# qo-100-digital-rf-power-meter.net
KiCad netlist of a schematic drawn in EAGLE
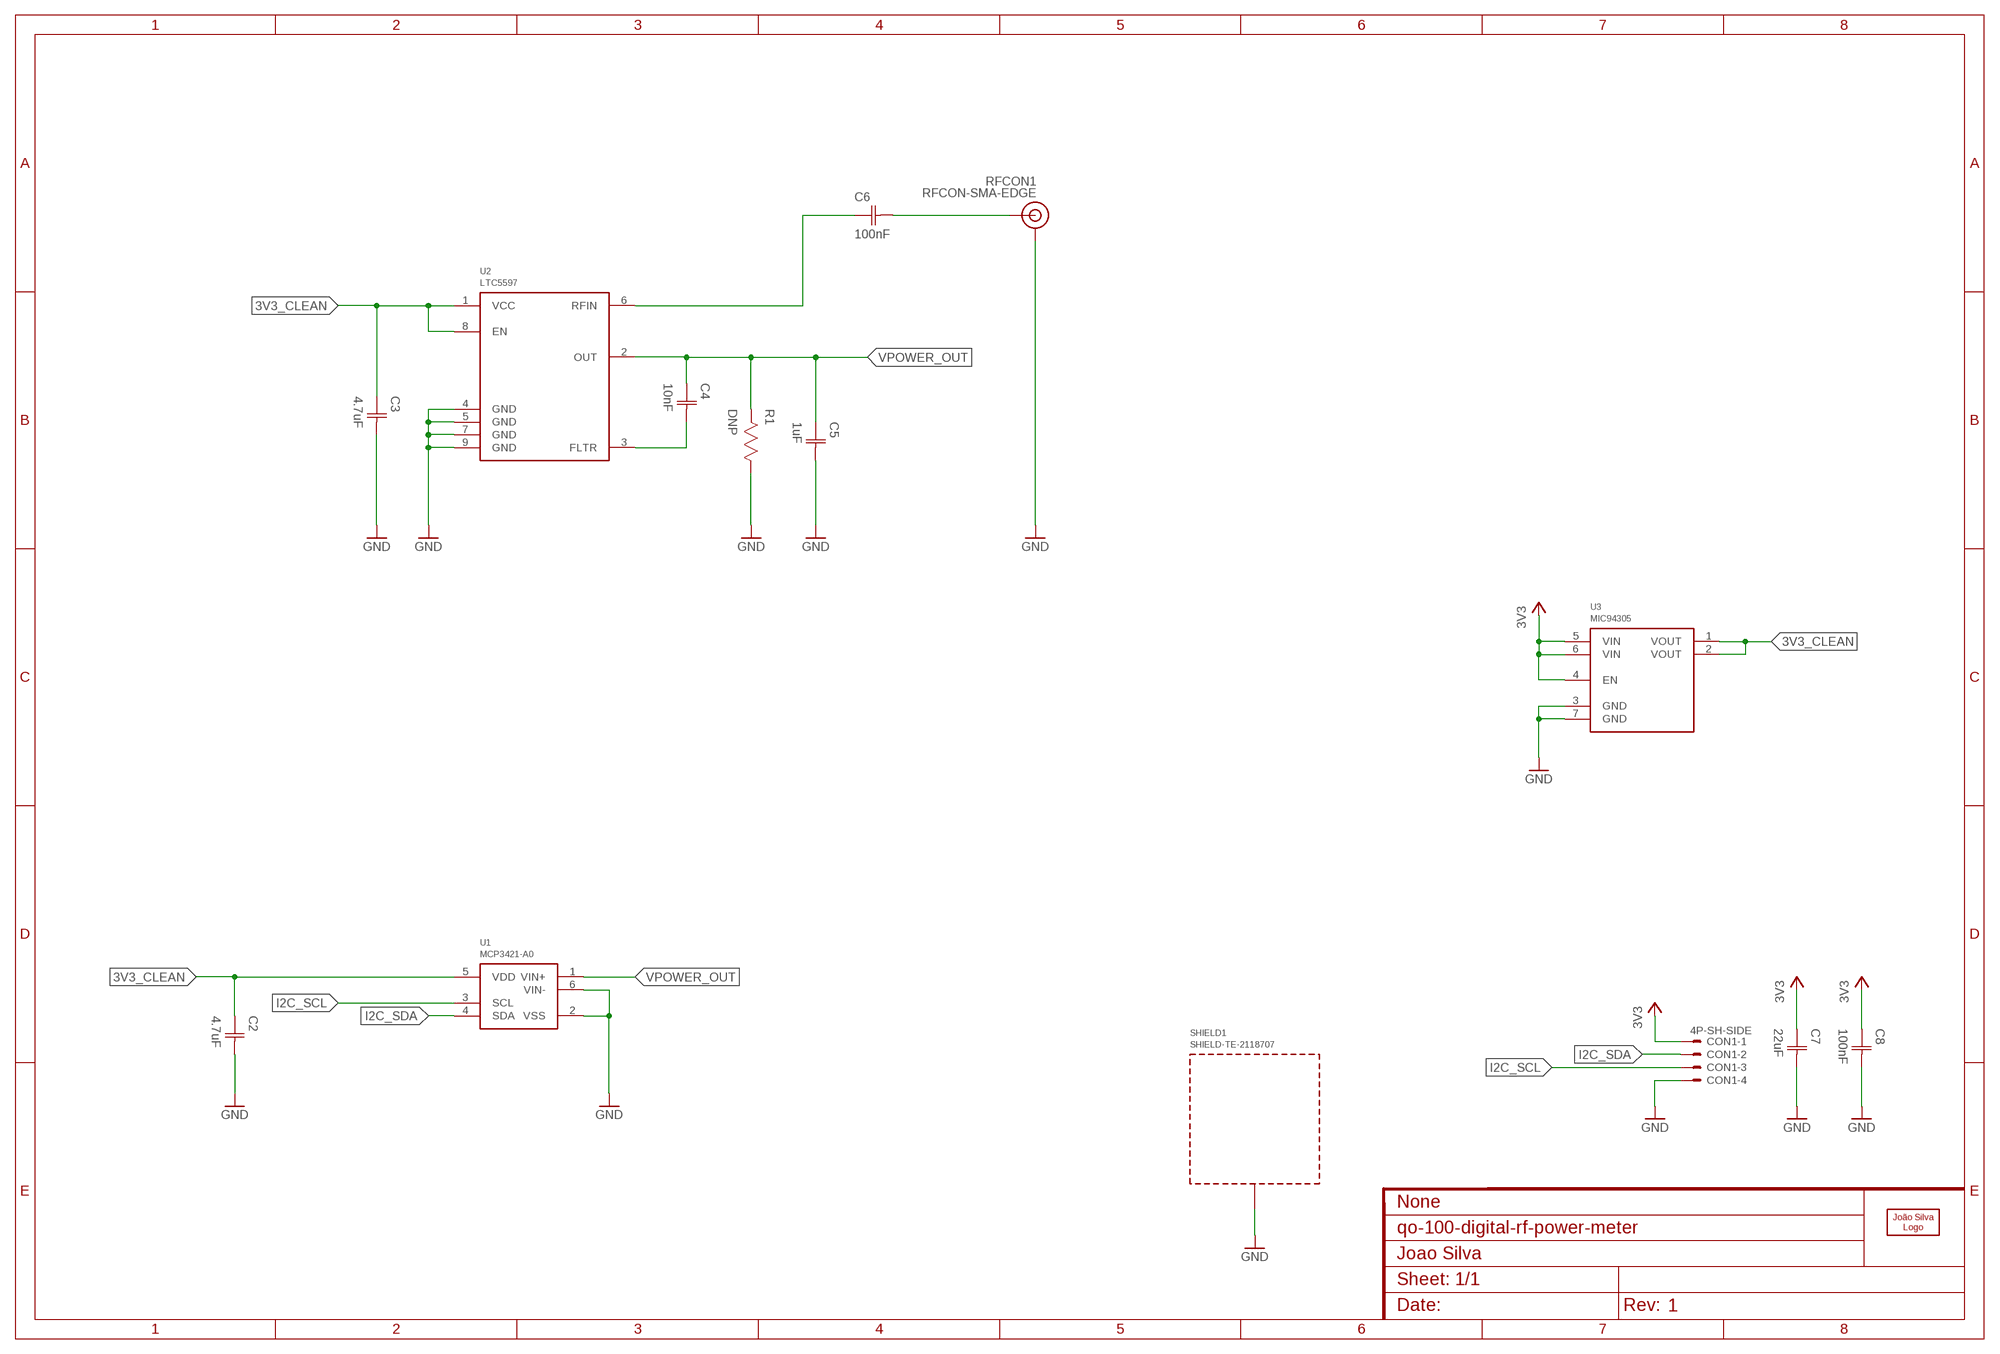
[diagram p0: schematic, sheet 1]

(export (version "E")
  (design (tool "Eeschema 10.0.6"))
  (components
    (comp (ref "C2")
      (value "4.7uF")
      (footprint "eagle-import:CAP0603")
      (libsource (lib "eagle-import") (part "CAPACITOR-0603"))
    )
    (comp (ref "C3")
      (value "4.7uF")
      (footprint "eagle-import:CAP0603")
      (libsource (lib "eagle-import") (part "CAPACITOR-0603"))
    )
    (comp (ref "C4")
      (value "10nF")
      (footprint "eagle-import:CAP0603")
      (libsource (lib "eagle-import") (part "CAPACITOR-0603"))
    )
    (comp (ref "C5")
      (value "1uF")
      (footprint "eagle-import:CAP0603")
      (libsource (lib "eagle-import") (part "CAPACITOR-0603"))
    )
    (comp (ref "C6")
      (value "100nF")
      (footprint "eagle-import:CAP0603")
      (libsource (lib "eagle-import") (part "CAPACITOR-0603"))
    )
    (comp (ref "C7")
      (value "22uF")
      (footprint "eagle-import:CAP1206")
      (libsource (lib "eagle-import") (part "CAPACITOR-1206"))
    )
    (comp (ref "C8")
      (value "100nF")
      (footprint "eagle-import:CAP0603")
      (libsource (lib "eagle-import") (part "CAPACITOR-0603"))
    )
    (comp (ref "CON1")
      (value "4P-SH-SIDE")
      (footprint "eagle-import:SH-04-SIDE")
      (libsource (lib "eagle-import") (part "4P-SH-SIDE"))
    )
    (comp (ref "LOGO1")
      (value "JS-5MM")
      (footprint "eagle-import:JS_5MM")
      (libsource (lib "eagle-import") (part "JS-5MM"))
    )
    (comp (ref "R1")
      (value "DNP")
      (footprint "eagle-import:RES0603")
      (libsource (lib "eagle-import") (part "RESISTOR-0603"))
    )
    (comp (ref "RFCON1")
      (value "RFCON-SMA-EDGE")
      (footprint "eagle-import:SMA-EDGE")
      (libsource (lib "eagle-import") (part "RFCON-SMA-EDGE"))
    )
    (comp (ref "SHIELD1")
      (value "SHIELD-TE-2118707")
      (footprint "eagle-import:2118707")
      (libsource (lib "eagle-import") (part "SHIELD-TE-2118707"))
    )
    (comp (ref "U1")
      (value "MCP3421-A0")
      (footprint "eagle-import:SOT23-6")
      (libsource (lib "eagle-import") (part "MCP3421-A0"))
    )
    (comp (ref "U2")
      (value "LTC5597")
      (footprint "eagle-import:DFN8_2X2")
      (libsource (lib "eagle-import") (part "LTC5597"))
    )
    (comp (ref "U3")
      (value "MIC94305")
      (footprint "eagle-import:DFN6")
      (libsource (lib "eagle-import") (part "MIC94305"))
    )
  )
  (nets
    (net (code "1") (name "3V3") (class "Default")
      (node (ref "C7") (pin "1") (pinfunction "C1_1") (pintype "passive"))
      (node (ref "C8") (pin "1") (pinfunction "C1_1") (pintype "passive"))
      (node (ref "CON1") (pin "1") (pinfunction "S_1") (pintype "passive"))
      (node (ref "U3") (pin "4") (pinfunction "EN_4") (pintype "bidirectional"))
      (node (ref "U3") (pin "5") (pinfunction "VIN_5") (pintype "bidirectional"))
      (node (ref "U3") (pin "6") (pinfunction "VIN_6") (pintype "bidirectional"))
    )
    (net (code "2") (name "3V3_CLEAN") (class "Default")
      (node (ref "C2") (pin "1") (pinfunction "C1_1") (pintype "passive"))
      (node (ref "C3") (pin "1") (pinfunction "C1_1") (pintype "passive"))
      (node (ref "U1") (pin "5") (pinfunction "VDD_5") (pintype "bidirectional"))
      (node (ref "U2") (pin "1") (pinfunction "VCC_1") (pintype "bidirectional"))
      (node (ref "U2") (pin "8") (pinfunction "EN_8") (pintype "bidirectional"))
      (node (ref "U3") (pin "1") (pinfunction "VOUT_1") (pintype "bidirectional"))
      (node (ref "U3") (pin "2") (pinfunction "VOUT_2") (pintype "bidirectional"))
    )
    (net (code "3") (name "GND") (class "Default")
      (node (ref "C2") (pin "2") (pinfunction "C2_2") (pintype "passive"))
      (node (ref "C3") (pin "2") (pinfunction "C2_2") (pintype "passive"))
      (node (ref "C5") (pin "2") (pinfunction "C2_2") (pintype "passive"))
      (node (ref "C7") (pin "2") (pinfunction "C2_2") (pintype "passive"))
      (node (ref "C8") (pin "2") (pinfunction "C2_2") (pintype "passive"))
      (node (ref "CON1") (pin "4") (pinfunction "S_4") (pintype "passive"))
      (node (ref "R1") (pin "1") (pinfunction "1_1") (pintype "passive"))
      (node (ref "RFCON1") (pin "GND@0") (pinfunction "GND_GND@0") (pintype "bidirectional"))
      (node (ref "RFCON1") (pin "GND@1") (pinfunction "GND_GND@1") (pintype "bidirectional"))
      (node (ref "RFCON1") (pin "GND@2") (pinfunction "GND_GND@2") (pintype "bidirectional"))
      (node (ref "RFCON1") (pin "GND@3") (pinfunction "GND_GND@3") (pintype "bidirectional"))
      (node (ref "SHIELD1") (pin "1") (pinfunction "GND_1") (pintype "bidirectional"))
      (node (ref "SHIELD1") (pin "10") (pinfunction "GND_10") (pintype "bidirectional"))
      (node (ref "SHIELD1") (pin "11") (pinfunction "GND_11") (pintype "bidirectional"))
      (node (ref "SHIELD1") (pin "12") (pinfunction "GND_12") (pintype "bidirectional"))
      (node (ref "SHIELD1") (pin "2") (pinfunction "GND_2") (pintype "bidirectional"))
      (node (ref "SHIELD1") (pin "3") (pinfunction "GND_3") (pintype "bidirectional"))
      (node (ref "SHIELD1") (pin "4") (pinfunction "GND_4") (pintype "bidirectional"))
      (node (ref "SHIELD1") (pin "5") (pinfunction "GND_5") (pintype "bidirectional"))
      (node (ref "SHIELD1") (pin "6") (pinfunction "GND_6") (pintype "bidirectional"))
      (node (ref "SHIELD1") (pin "7") (pinfunction "GND_7") (pintype "bidirectional"))
      (node (ref "SHIELD1") (pin "8") (pinfunction "GND_8") (pintype "bidirectional"))
      (node (ref "SHIELD1") (pin "9") (pinfunction "GND_9") (pintype "bidirectional"))
      (node (ref "U1") (pin "2") (pinfunction "VSS_2") (pintype "bidirectional"))
      (node (ref "U1") (pin "6") (pinfunction "VIN-_6") (pintype "bidirectional"))
      (node (ref "U2") (pin "4") (pinfunction "GND_4") (pintype "bidirectional"))
      (node (ref "U2") (pin "5") (pinfunction "GND_5") (pintype "bidirectional"))
      (node (ref "U2") (pin "7") (pinfunction "GND_7") (pintype "bidirectional"))
      (node (ref "U2") (pin "9") (pinfunction "GND_9") (pintype "bidirectional"))
      (node (ref "U3") (pin "3") (pinfunction "GND_3") (pintype "bidirectional"))
      (node (ref "U3") (pin "7") (pinfunction "GND_7") (pintype "bidirectional"))
    )
    (net (code "4") (name "I2C_SCL") (class "Default")
      (node (ref "CON1") (pin "3") (pinfunction "S_3") (pintype "passive"))
      (node (ref "U1") (pin "3") (pinfunction "SCL_3") (pintype "bidirectional"))
    )
    (net (code "5") (name "I2C_SDA") (class "Default")
      (node (ref "CON1") (pin "2") (pinfunction "S_2") (pintype "passive"))
      (node (ref "U1") (pin "4") (pinfunction "SDA_4") (pintype "bidirectional"))
    )
    (net (code "6") (name "Net-(C4-C2)") (class "Default")
      (node (ref "C4") (pin "2") (pinfunction "C2_2") (pintype "passive"))
      (node (ref "U2") (pin "3") (pinfunction "FLTR_3") (pintype "bidirectional"))
    )
    (net (code "7") (name "Net-(C6-C1)") (class "Default")
      (node (ref "C6") (pin "1") (pinfunction "C1_1") (pintype "passive"))
      (node (ref "U2") (pin "6") (pinfunction "RFIN_6") (pintype "bidirectional"))
    )
    (net (code "8") (name "Net-(C6-C2)") (class "Default")
      (node (ref "C6") (pin "2") (pinfunction "C2_2") (pintype "passive"))
      (node (ref "RFCON1") (pin "SIG") (pinfunction "SIGNAL_SIG") (pintype "bidirectional"))
    )
    (net (code "9") (name "VPOWER_OUT") (class "Default")
      (node (ref "C4") (pin "1") (pinfunction "C1_1") (pintype "passive"))
      (node (ref "C5") (pin "1") (pinfunction "C1_1") (pintype "passive"))
      (node (ref "R1") (pin "2") (pinfunction "2_2") (pintype "passive"))
      (node (ref "U1") (pin "1") (pinfunction "VIN+_1") (pintype "bidirectional"))
      (node (ref "U2") (pin "2") (pinfunction "OUT_2") (pintype "bidirectional"))
    )
  )
)
